# openSX70_ALPHA_V6-20181005.net
KiCad netlist of a schematic drawn in EAGLE
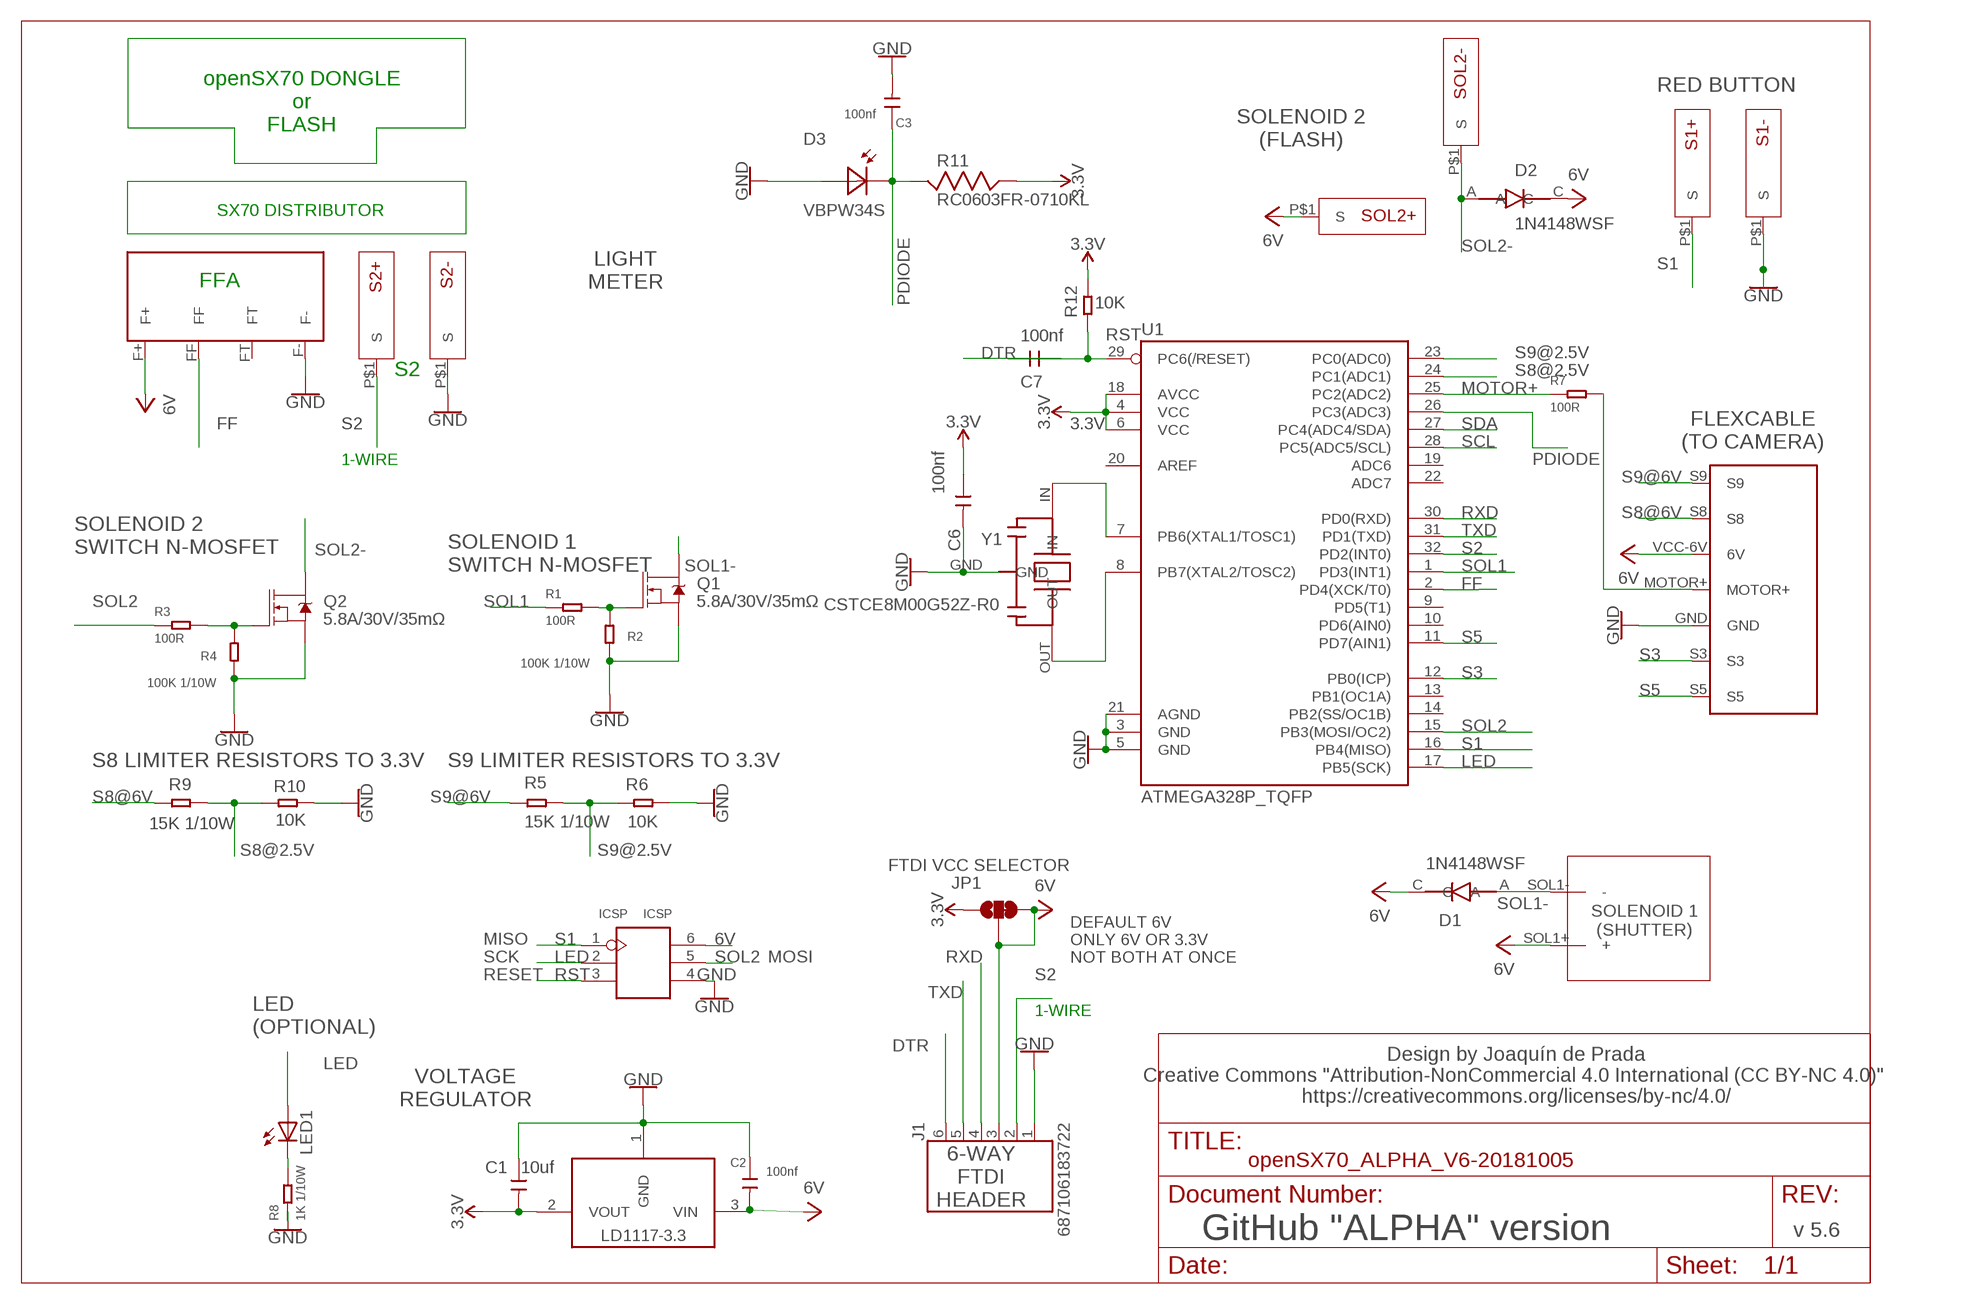
[diagram p0: schematic, sheet 1]

(export (version "E")
  (design (tool "Eeschema 10.0.6"))
  (components
    (comp (ref "C1")
      (value "10uf")
      (footprint "eagle-import:C0603")
      (fields (field (name "MPN") "CC0603KRX5R6BB106"))
      (libsource (lib "eagle-import") (part "CERAMIC-10UF-10V-10%-X5R(0603)"))
    )
    (comp (ref "C2")
      (value "100nf")
      (footprint "eagle-import:C0603")
      (fields (field (name "MPN") "CC0603KRX7R9BB104"))
      (libsource (lib "eagle-import") (part "CERAMIC-100NF-50V-10%-X7R(0603)"))
    )
    (comp (ref "C3")
      (value "100nf")
      (footprint "eagle-import:C0603")
      (fields (field (name "MPN") "CC0603KRX7R9BB104"))
      (libsource (lib "eagle-import") (part "CERAMIC-100NF-50V-10%-X7R(0603)"))
    )
    (comp (ref "C6")
      (value "100nf")
      (footprint "eagle-import:C0603")
      (fields (field (name "MPN") "CC0603KRX7R9BB104"))
      (libsource (lib "eagle-import") (part "CERAMIC-100NF-50V-10%-X7R(0603)"))
    )
    (comp (ref "C7")
      (value "100nf")
      (footprint "eagle-import:C0603")
      (fields (field (name "MPN") "CC0603KRX7R9BB104"))
      (libsource (lib "eagle-import") (part "CERAMIC-100NF-50V-10%-X7R(0603)"))
    )
    (comp (ref "D1")
      (value "1N4148WSF")
      (footprint "eagle-import:SODFL2512X100N")
      (fields (field (name "MANUFACTURER") "Fairchild Semiconductor"))
      (libsource (lib "eagle-import") (part "1N4148WS"))
    )
    (comp (ref "D2")
      (value "1N4148WSF")
      (footprint "eagle-import:SODFL2512X100N")
      (fields (field (name "MANUFACTURER") "Fairchild Semiconductor"))
      (libsource (lib "eagle-import") (part "1N4148WS"))
    )
    (comp (ref "D3")
      (value "VBPW34S")
      (footprint "eagle-import:SOD6439X130N")
      (fields (field (name "DIGI-KEY_PART_NUMBER") "751-1500-1-ND") (field (name "MF") "Vishay"))
      (libsource (lib "eagle-import") (part "VBPW34S"))
    )
    (comp (ref "ICSP")
      (value "ICSP")
      (footprint "eagle-import:H2X3-2.54")
      (libsource (lib "eagle-import") (part "ICSP"))
    )
    (comp (ref "J1")
      (value "687106183722")
      (footprint "eagle-import:687106183722")
      (fields (field (name "MF") "Wurth Electronics"))
      (libsource (lib "eagle-import") (part "687106183722"))
    )
    (comp (ref "JP1")
      (value "FTDI VCC SELECTOR")
      (footprint "eagle-import:SMT-JUMPER_3_1-NC_TRACE_SILK")
      (libsource (lib "eagle-import") (part "JUMPER-SMT_3_1-NC_TRACE_SILK"))
    )
    (comp (ref "LD11172.5V")
      (value "LD1117 2.5V")
      (footprint "eagle-import:SOT223")
      (fields (field (name "MF") "Advanced Monolithic Systems") (field (name "MP") "AMS1117-5.0"))
      (libsource (lib "eagle-import") (part "LD1117-3.3"))
    )
    (comp (ref "LED1")
      (value "LEDCHIPLED_0805")
      (footprint "eagle-import:CHIPLED_0805")
      (libsource (lib "eagle-import") (part "LEDCHIPLED_0805"))
    )
    (comp (ref "Q1")
      (value "5.8A/30V/35mΩ")
      (footprint "eagle-import:SOT23-3")
      (libsource (lib "eagle-import") (part "MOSFET-NCH-AO3404A"))
    )
    (comp (ref "Q2")
      (value "5.8A/30V/35mΩ")
      (footprint "eagle-import:SOT23-3")
      (libsource (lib "eagle-import") (part "MOSFET-NCH-AO3404A"))
    )
    (comp (ref "R1")
      (value "100R")
      (footprint "eagle-import:R0603")
      (fields (field (name "MPN") "RC0603JR-07100RL"))
      (libsource (lib "eagle-import") (part "SMD-RES-100R-5%-1/10W(0603)"))
    )
    (comp (ref "R2")
      (value "100K 1/10W")
      (footprint "eagle-import:R0603")
      (fields (field (name "MPN") "RC0603JR-07100KL"))
      (libsource (lib "eagle-import") (part "SMD-RES-100K-5%-1/10W(0603)"))
    )
    (comp (ref "R3")
      (value "100R")
      (footprint "eagle-import:R0603")
      (fields (field (name "MPN") "RC0603JR-07100RL"))
      (libsource (lib "eagle-import") (part "SMD-RES-100R-5%-1/10W(0603)"))
    )
    (comp (ref "R4")
      (value "100K 1/10W")
      (footprint "eagle-import:R0603")
      (fields (field (name "MPN") "RC0603JR-07100KL"))
      (libsource (lib "eagle-import") (part "SMD-RES-100K-5%-1/10W(0603)"))
    )
    (comp (ref "R5")
      (value "15K 1/10W")
      (footprint "eagle-import:R0603")
      (fields (field (name "MPN") "RC0603FR-0715KL"))
      (libsource (lib "eagle-import") (part "SMD-RES-15K-1%-1/10W(0603)"))
    )
    (comp (ref "R6")
      (value "10K")
      (footprint "eagle-import:R0603")
      (fields (field (name "MPN") "RC0603FR-0710KL"))
      (libsource (lib "eagle-import") (part "SMD-RES-10K-1%-1/10W(0603)"))
    )
    (comp (ref "R7")
      (value "100R")
      (footprint "eagle-import:R0603")
      (fields (field (name "MPN") "RC0603JR-07100RL"))
      (libsource (lib "eagle-import") (part "SMD-RES-100R-5%-1/10W(0603)"))
    )
    (comp (ref "R8")
      (value "1K 1/10W")
      (footprint "eagle-import:R0603")
      (fields (field (name "MPN") "RC0603JR-071KL"))
      (libsource (lib "eagle-import") (part "SMD-RES-1K-5%-1/10W(0603)"))
    )
    (comp (ref "R9")
      (value "15K 1/10W")
      (footprint "eagle-import:R0603")
      (fields (field (name "MPN") "RC0603FR-0715KL"))
      (libsource (lib "eagle-import") (part "SMD-RES-15K-1%-1/10W(0603)"))
    )
    (comp (ref "R10")
      (value "10K")
      (footprint "eagle-import:R0603")
      (fields (field (name "MPN") "RC0603FR-0710KL"))
      (libsource (lib "eagle-import") (part "SMD-RES-10K-1%-1/10W(0603)"))
    )
    (comp (ref "R11")
      (value "RC0603FR-0710KL")
      (footprint "eagle-import:RC0603FR-0710KL_RESC1608X55")
      (fields (field (name "MANUFACTURER") "YAGEO"))
      (libsource (lib "eagle-import") (part "RC0603FR-0710KL"))
    )
    (comp (ref "R12")
      (value "10K")
      (footprint "eagle-import:R0603")
      (fields (field (name "MPN") "RC0603FR-0710KL"))
      (libsource (lib "eagle-import") (part "SMD-RES-10K-1%-1/10W(0603)"))
    )
    (comp (ref "S1+")
      (value "SX70-S-PAD-NEW")
      (footprint "eagle-import:SX70-S-PAD2")
      (libsource (lib "eagle-import") (part "SX70-S-PAD-NEW"))
    )
    (comp (ref "S1-")
      (value "SX70-S-PAD-NEW")
      (footprint "eagle-import:SX70-S-PAD2")
      (libsource (lib "eagle-import") (part "SX70-S-PAD-NEW"))
    )
    (comp (ref "S2+")
      (value "SX70-S-PAD-NEW")
      (footprint "eagle-import:SX70-S-PAD2")
      (libsource (lib "eagle-import") (part "SX70-S-PAD-NEW"))
    )
    (comp (ref "S2-")
      (value "SX70-S-PAD-NEW")
      (footprint "eagle-import:SX70-S-PAD2")
      (libsource (lib "eagle-import") (part "SX70-S-PAD-NEW"))
    )
    (comp (ref "SOL1")
      (value "SX70-SOLENOID1-2PADS")
      (footprint "eagle-import:SX70-SOLENOID1-2")
      (libsource (lib "eagle-import") (part "SX70-SOLENOID1-2PADS"))
    )
    (comp (ref "SOL2+")
      (value "SX70-S-PAD-NEW")
      (footprint "eagle-import:SX70-S-PAD2")
      (libsource (lib "eagle-import") (part "SX70-S-PAD-NEW"))
    )
    (comp (ref "SOL2-")
      (value "SX70-S-PAD-NEW")
      (footprint "eagle-import:SX70-S-PAD2")
      (libsource (lib "eagle-import") (part "SX70-S-PAD-NEW"))
    )
    (comp (ref "U$1")
      (value "SX70-7-PAD")
      (footprint "eagle-import:SX70-7-PAD")
      (libsource (lib "eagle-import") (part "SX70-7-PAD"))
    )
    (comp (ref "U$2")
      (value "FFA")
      (footprint "eagle-import:FFA-PAD-PACKAGE")
      (libsource (lib "eagle-import") (part "SX70-FFA-PAD"))
    )
    (comp (ref "U1")
      (value "ATMEGA328P_TQFP")
      (footprint "eagle-import:TQFP32-08")
      (libsource (lib "eagle-import") (part "ATMEGA328P_TQFP"))
    )
    (comp (ref "Y1")
      (value "CSTCE8M00G52Z-R0")
      (footprint "eagle-import:CFP95P160X100-3N")
      (fields (field (name "MF") "Murata") (field (name "MP") "CSTCE16M0V53-R0"))
      (libsource (lib "eagle-import") (part "CSTCE16M0V53-R0"))
    )
  )
  (nets
    (net (code "1") (name "/DTR") (class "Default")
      (node (ref "C7") (pin "1") (pinfunction "1_1") (pintype "passive"))
      (node (ref "J1") (pin "6") (pinfunction "1_6") (pintype "passive"))
    )
    (net (code "2") (name "/FF") (class "Default")
      (node (ref "U$2") (pin "FF") (pinfunction "FF_FF") (pintype "bidirectional"))
      (node (ref "U1") (pin "2") (pinfunction "PD4(XCK/T0)_2") (pintype "bidirectional"))
    )
    (net (code "3") (name "/LED") (class "Default")
      (node (ref "ICSP") (pin "2") (pinfunction "SCK_2") (pintype "bidirectional"))
      (node (ref "LED1") (pin "A") (pinfunction "A_A") (pintype "passive"))
      (node (ref "U1") (pin "17") (pinfunction "PB5(SCK)_17") (pintype "bidirectional"))
    )
    (net (code "4") (name "/MOTOR+") (class "Default")
      (node (ref "R7") (pin "1") (pinfunction "1_1") (pintype "passive"))
      (node (ref "U1") (pin "25") (pinfunction "PC2(ADC2)_25") (pintype "bidirectional"))
    )
    (net (code "5") (name "/PDIODE") (class "Default")
      (node (ref "C3") (pin "1") (pinfunction "1_1") (pintype "passive"))
      (node (ref "D3") (pin "C") (pinfunction "C_C") (pintype "passive"))
      (node (ref "R11") (pin "1") (pinfunction "1_1") (pintype "passive"))
      (node (ref "U1") (pin "26") (pinfunction "PC3(ADC3)_26") (pintype "bidirectional"))
    )
    (net (code "6") (name "/RST") (class "Default")
      (node (ref "C7") (pin "2") (pinfunction "2_2") (pintype "passive"))
      (node (ref "ICSP") (pin "3") (pinfunction "RST_3") (pintype "bidirectional"))
      (node (ref "R12") (pin "1") (pinfunction "1_1") (pintype "passive"))
      (node (ref "U1") (pin "29") (pinfunction "PC6(/RESET)_29") (pintype "bidirectional"))
    )
    (net (code "7") (name "/RXD") (class "Default")
      (node (ref "J1") (pin "4") (pinfunction "3_4") (pintype "passive"))
      (node (ref "U1") (pin "30") (pinfunction "PD0(RXD)_30") (pintype "bidirectional"))
    )
    (net (code "8") (name "/S1") (class "Default")
      (node (ref "ICSP") (pin "1") (pinfunction "MISO_1") (pintype "bidirectional"))
      (node (ref "S1+") (pin "P$1") (pinfunction "S_P$1") (pintype "bidirectional"))
      (node (ref "U1") (pin "16") (pinfunction "PB4(MISO)_16") (pintype "bidirectional"))
    )
    (net (code "9") (name "/S2") (class "Default")
      (node (ref "J1") (pin "2") (pinfunction "5_2") (pintype "passive"))
      (node (ref "S2+") (pin "P$1") (pinfunction "S_P$1") (pintype "bidirectional"))
      (node (ref "U1") (pin "32") (pinfunction "PD2(INT0)_32") (pintype "bidirectional"))
    )
    (net (code "10") (name "/S3") (class "Default")
      (node (ref "U$1") (pin "S3") (pinfunction "S3_S3") (pintype "bidirectional"))
      (node (ref "U1") (pin "12") (pinfunction "PB0(ICP)_12") (pintype "bidirectional"))
    )
    (net (code "11") (name "/S5") (class "Default")
      (node (ref "U$1") (pin "S5") (pinfunction "S5_S5") (pintype "bidirectional"))
      (node (ref "U1") (pin "11") (pinfunction "PD7(AIN1)_11") (pintype "bidirectional"))
    )
    (net (code "12") (name "/S8@2.5V") (class "Default")
      (node (ref "R10") (pin "1") (pinfunction "1_1") (pintype "passive"))
      (node (ref "R9") (pin "2") (pinfunction "2_2") (pintype "passive"))
      (node (ref "U1") (pin "24") (pinfunction "PC1(ADC1)_24") (pintype "bidirectional"))
    )
    (net (code "13") (name "/S8@6V") (class "Default")
      (node (ref "R9") (pin "1") (pinfunction "1_1") (pintype "passive"))
      (node (ref "U$1") (pin "S8") (pinfunction "S8_S8") (pintype "bidirectional"))
    )
    (net (code "14") (name "/S9@2.5V") (class "Default")
      (node (ref "R5") (pin "2") (pinfunction "2_2") (pintype "passive"))
      (node (ref "R6") (pin "1") (pinfunction "1_1") (pintype "passive"))
      (node (ref "U1") (pin "23") (pinfunction "PC0(ADC0)_23") (pintype "bidirectional"))
    )
    (net (code "15") (name "/S9@6V") (class "Default")
      (node (ref "R5") (pin "1") (pinfunction "1_1") (pintype "passive"))
      (node (ref "U$1") (pin "S9") (pinfunction "S9_S9") (pintype "bidirectional"))
    )
    (net (code "16") (name "/SCL") (class "Default")
      (node (ref "U1") (pin "28") (pinfunction "PC5(ADC5/SCL)_28") (pintype "bidirectional"))
    )
    (net (code "17") (name "/SDA") (class "Default")
      (node (ref "U1") (pin "27") (pinfunction "PC4(ADC4/SDA)_27") (pintype "bidirectional"))
    )
    (net (code "18") (name "/SOL1") (class "Default")
      (node (ref "R1") (pin "1") (pinfunction "1_1") (pintype "passive"))
      (node (ref "U1") (pin "1") (pinfunction "PD3(INT1)_1") (pintype "bidirectional"))
    )
    (net (code "19") (name "/SOL1-") (class "Default")
      (node (ref "D1") (pin "A") (pinfunction "A_A") (pintype "passive"))
      (node (ref "Q1") (pin "3") (pinfunction "D_3") (pintype "bidirectional"))
      (node (ref "SOL1") (pin "SOL1-") (pinfunction "-_SOL1-") (pintype "bidirectional"))
    )
    (net (code "20") (name "/SOL2") (class "Default")
      (node (ref "ICSP") (pin "5") (pinfunction "MOSI_5") (pintype "bidirectional"))
      (node (ref "R3") (pin "1") (pinfunction "1_1") (pintype "passive"))
      (node (ref "U1") (pin "15") (pinfunction "PB3(MOSI/OC2)_15") (pintype "bidirectional"))
    )
    (net (code "21") (name "/SOL2-") (class "Default")
      (node (ref "D2") (pin "A") (pinfunction "A_A") (pintype "passive"))
      (node (ref "Q2") (pin "3") (pinfunction "D_3") (pintype "bidirectional"))
      (node (ref "SOL2-") (pin "P$1") (pinfunction "S_P$1") (pintype "bidirectional"))
    )
    (net (code "22") (name "/TXD") (class "Default")
      (node (ref "J1") (pin "5") (pinfunction "2_5") (pintype "passive"))
      (node (ref "U1") (pin "31") (pinfunction "PD1(TXD)_31") (pintype "bidirectional"))
    )
    (net (code "23") (name "3.3V") (class "Default")
      (node (ref "C1") (pin "2") (pinfunction "2_2") (pintype "passive"))
      (node (ref "C6") (pin "1") (pinfunction "1_1") (pintype "passive"))
      (node (ref "JP1") (pin "1") (pinfunction "1_1") (pintype "passive"))
      (node (ref "LD11172.5V") (pin "2") (pinfunction "VOUT_2") (pintype "bidirectional"))
      (node (ref "R11") (pin "2") (pinfunction "2_2") (pintype "passive"))
      (node (ref "R12") (pin "2") (pinfunction "2_2") (pintype "passive"))
      (node (ref "U1") (pin "18") (pinfunction "AVCC_18") (pintype "bidirectional"))
      (node (ref "U1") (pin "4") (pinfunction "VCC_4") (pintype "bidirectional"))
      (node (ref "U1") (pin "6") (pinfunction "VCC_6") (pintype "bidirectional"))
    )
    (net (code "24") (name "6V") (class "Default")
      (node (ref "C2") (pin "2") (pinfunction "2_2") (pintype "passive"))
      (node (ref "D1") (pin "C") (pinfunction "C_C") (pintype "passive"))
      (node (ref "D2") (pin "C") (pinfunction "C_C") (pintype "passive"))
      (node (ref "ICSP") (pin "6") (pinfunction "VCC_6") (pintype "bidirectional"))
      (node (ref "J1") (pin "3") (pinfunction "4_3") (pintype "passive"))
      (node (ref "JP1") (pin "2") (pinfunction "2_2") (pintype "passive"))
      (node (ref "JP1") (pin "3") (pinfunction "3_3") (pintype "passive"))
      (node (ref "LD11172.5V") (pin "3") (pinfunction "VIN_3") (pintype "bidirectional"))
      (node (ref "SOL1") (pin "SOL1+") (pinfunction "+_SOL1+") (pintype "bidirectional"))
      (node (ref "SOL2+") (pin "P$1") (pinfunction "S_P$1") (pintype "bidirectional"))
      (node (ref "U$1") (pin "VCC-6V") (pinfunction "6V_VCC-6V") (pintype "bidirectional"))
      (node (ref "U$2") (pin "F+") (pinfunction "F+_F+") (pintype "bidirectional"))
    )
    (net (code "25") (name "GND") (class "Default")
      (node (ref "C1") (pin "1") (pinfunction "1_1") (pintype "passive"))
      (node (ref "C2") (pin "1") (pinfunction "1_1") (pintype "passive"))
      (node (ref "C3") (pin "2") (pinfunction "2_2") (pintype "passive"))
      (node (ref "C6") (pin "2") (pinfunction "2_2") (pintype "passive"))
      (node (ref "D3") (pin "A") (pinfunction "A_A") (pintype "passive"))
      (node (ref "ICSP") (pin "4") (pinfunction "GND_4") (pintype "bidirectional"))
      (node (ref "J1") (pin "1") (pinfunction "6_1") (pintype "passive"))
      (node (ref "LD11172.5V") (pin "1") (pinfunction "GND_1") (pintype "bidirectional"))
      (node (ref "Q1") (pin "2") (pinfunction "S_2") (pintype "bidirectional"))
      (node (ref "Q2") (pin "2") (pinfunction "S_2") (pintype "bidirectional"))
      (node (ref "R10") (pin "2") (pinfunction "2_2") (pintype "passive"))
      (node (ref "R2") (pin "1") (pinfunction "1_1") (pintype "passive"))
      (node (ref "R4") (pin "1") (pinfunction "1_1") (pintype "passive"))
      (node (ref "R6") (pin "2") (pinfunction "2_2") (pintype "passive"))
      (node (ref "R8") (pin "1") (pinfunction "1_1") (pintype "passive"))
      (node (ref "S1-") (pin "P$1") (pinfunction "S_P$1") (pintype "bidirectional"))
      (node (ref "S2-") (pin "P$1") (pinfunction "S_P$1") (pintype "bidirectional"))
      (node (ref "U$1") (pin "GND") (pinfunction "GND_GND") (pintype "bidirectional"))
      (node (ref "U$2") (pin "F-") (pinfunction "F-_F-") (pintype "bidirectional"))
      (node (ref "U1") (pin "21") (pinfunction "AGND_21") (pintype "bidirectional"))
      (node (ref "U1") (pin "3") (pinfunction "GND_3") (pintype "bidirectional"))
      (node (ref "U1") (pin "5") (pinfunction "GND_5") (pintype "bidirectional"))
      (node (ref "Y1") (pin "GND") (pinfunction "GND_GND") (pintype "passive"))
    )
    (net (code "26") (name "Net-(LED1-PadC)") (class "Default")
      (node (ref "LED1") (pin "C") (pinfunction "C_C") (pintype "passive"))
      (node (ref "R8") (pin "2") (pinfunction "2_2") (pintype "passive"))
    )
    (net (code "27") (name "Net-(Q1-G)") (class "Default")
      (node (ref "Q1") (pin "1") (pinfunction "G_1") (pintype "bidirectional"))
      (node (ref "R1") (pin "2") (pinfunction "2_2") (pintype "passive"))
      (node (ref "R2") (pin "2") (pinfunction "2_2") (pintype "passive"))
    )
    (net (code "28") (name "Net-(Q2-G)") (class "Default")
      (node (ref "Q2") (pin "1") (pinfunction "G_1") (pintype "bidirectional"))
      (node (ref "R3") (pin "2") (pinfunction "2_2") (pintype "passive"))
      (node (ref "R4") (pin "2") (pinfunction "2_2") (pintype "passive"))
    )
    (net (code "29") (name "Net-(R7-Pad2)") (class "Default")
      (node (ref "R7") (pin "2") (pinfunction "2_2") (pintype "passive"))
      (node (ref "U$1") (pin "MOTOR+") (pinfunction "MOTOR+_MOTOR+") (pintype "bidirectional"))
    )
    (net (code "30") (name "Net-(U1-PB6(XTAL1{slash}TOSC1))") (class "Default")
      (node (ref "U1") (pin "7") (pinfunction "PB6(XTAL1/TOSC1)_7") (pintype "bidirectional"))
      (node (ref "Y1") (pin "IN") (pinfunction "IN_IN") (pintype "input"))
    )
    (net (code "31") (name "Net-(U1-PB7(XTAL2{slash}TOSC2))") (class "Default")
      (node (ref "U1") (pin "8") (pinfunction "PB7(XTAL2/TOSC2)_8") (pintype "bidirectional"))
      (node (ref "Y1") (pin "OUT") (pinfunction "OUT_OUT") (pintype "output"))
    )
    (net (code "32") (name "unconnected-(U$2-PadFT)") (class "Default")
      (node (ref "U$2") (pin "FT") (pinfunction "FT_FT") (pintype "bidirectional"))
    )
    (net (code "33") (name "unconnected-(U1-ADC6-Pad19)") (class "Default")
      (node (ref "U1") (pin "19") (pinfunction "ADC6_19") (pintype "bidirectional"))
    )
    (net (code "34") (name "unconnected-(U1-ADC7-Pad22)") (class "Default")
      (node (ref "U1") (pin "22") (pinfunction "ADC7_22") (pintype "bidirectional"))
    )
    (net (code "35") (name "unconnected-(U1-AREF-Pad20)") (class "Default")
      (node (ref "U1") (pin "20") (pinfunction "AREF_20") (pintype "bidirectional"))
    )
    (net (code "36") (name "unconnected-(U1-PB1(OC1A)-Pad13)") (class "Default")
      (node (ref "U1") (pin "13") (pinfunction "PB1(OC1A)_13") (pintype "bidirectional"))
    )
    (net (code "37") (name "unconnected-(U1-PB2(SS{slash}OC1B)-Pad14)") (class "Default")
      (node (ref "U1") (pin "14") (pinfunction "PB2(SS/OC1B)_14") (pintype "bidirectional"))
    )
    (net (code "38") (name "unconnected-(U1-PD5(T1)-Pad9)") (class "Default")
      (node (ref "U1") (pin "9") (pinfunction "PD5(T1)_9") (pintype "bidirectional"))
    )
    (net (code "39") (name "unconnected-(U1-PD6(AIN0)-Pad10)") (class "Default")
      (node (ref "U1") (pin "10") (pinfunction "PD6(AIN0)_10") (pintype "bidirectional"))
    )
  )
)
